# BreakoutBoard.net
KiCad netlist of a schematic drawn in EAGLE
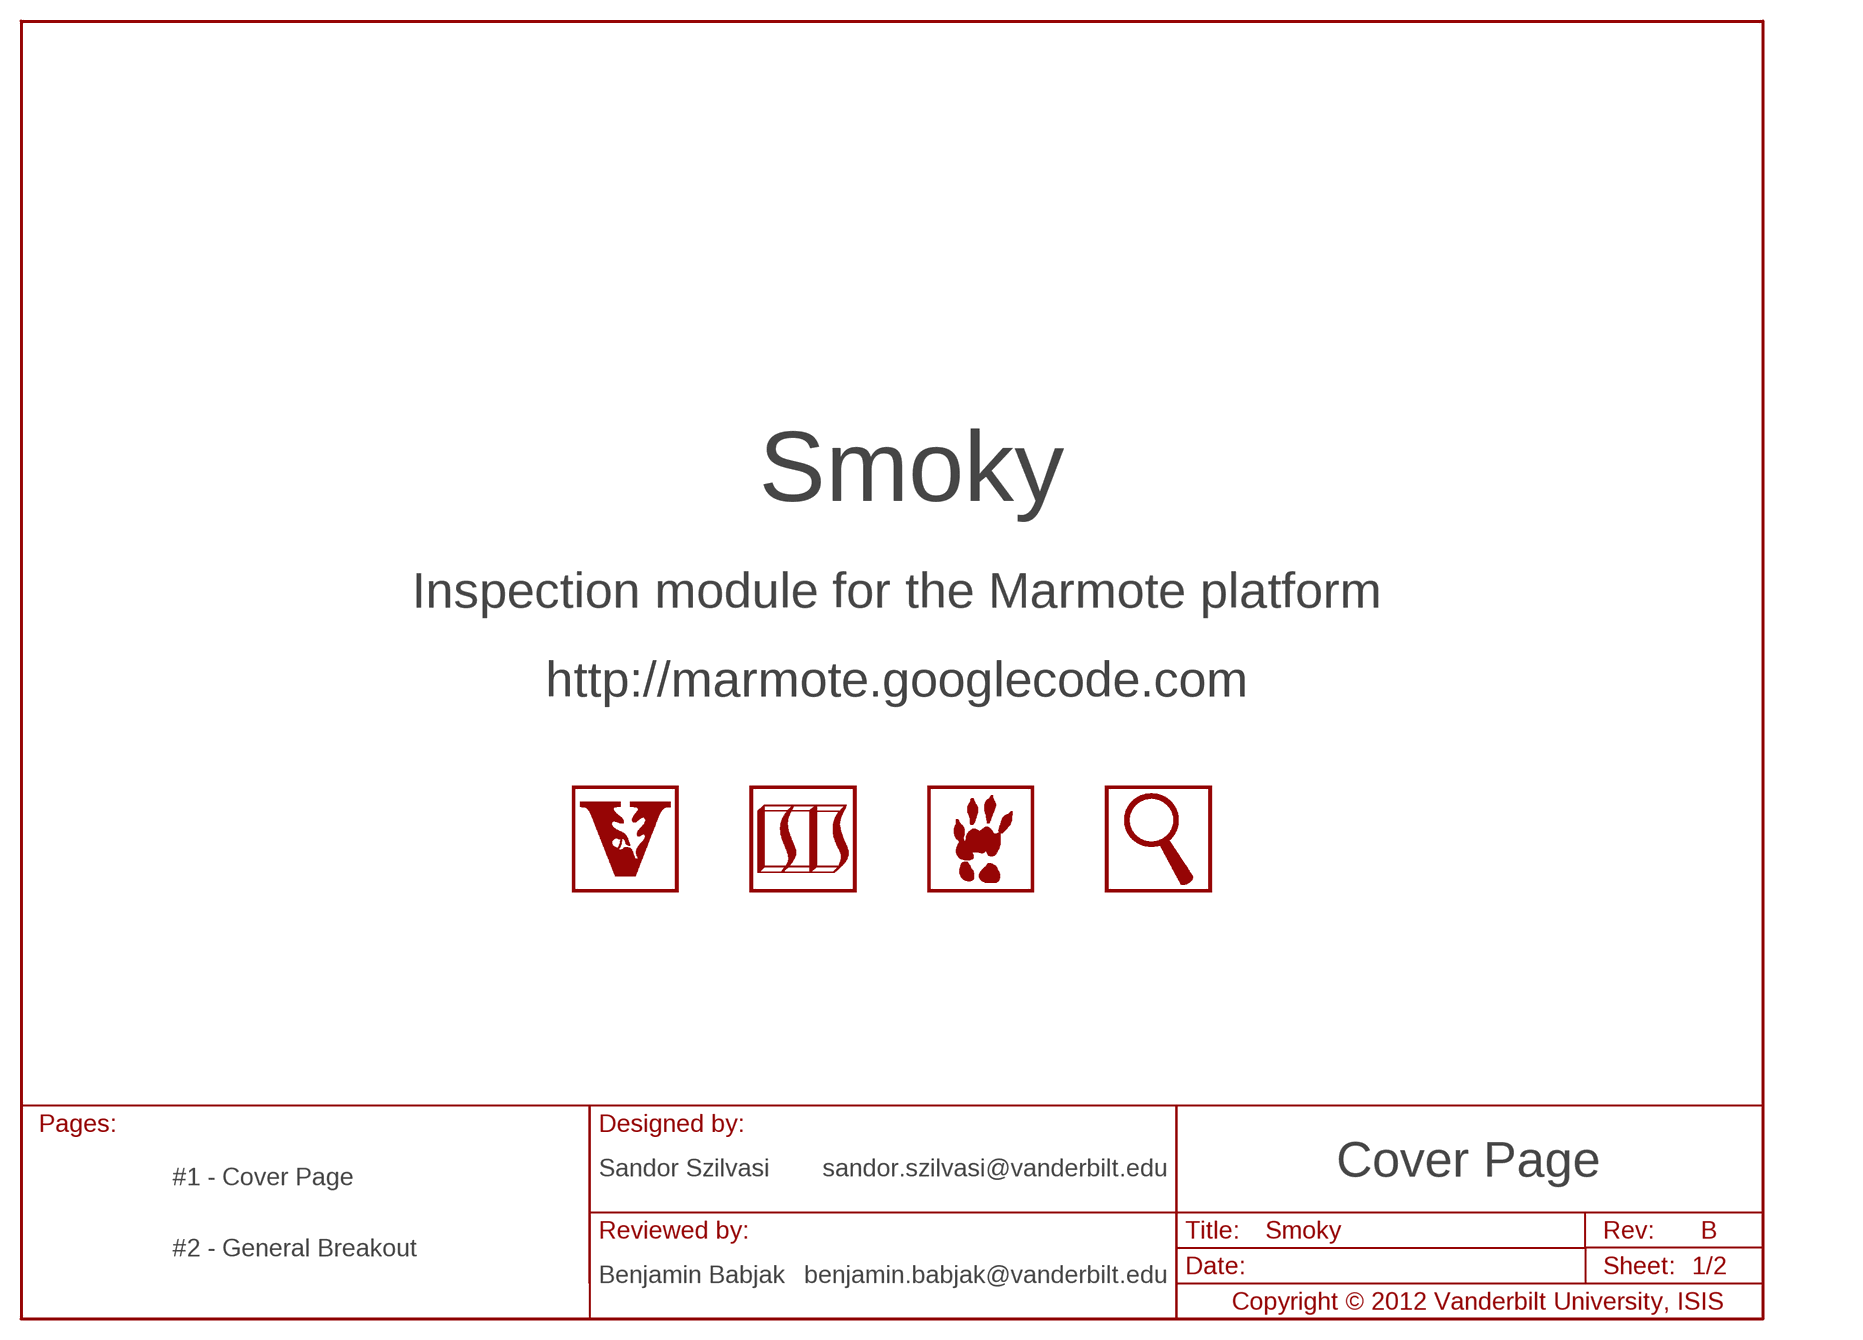
[diagram p0: schematic, sheet 1]
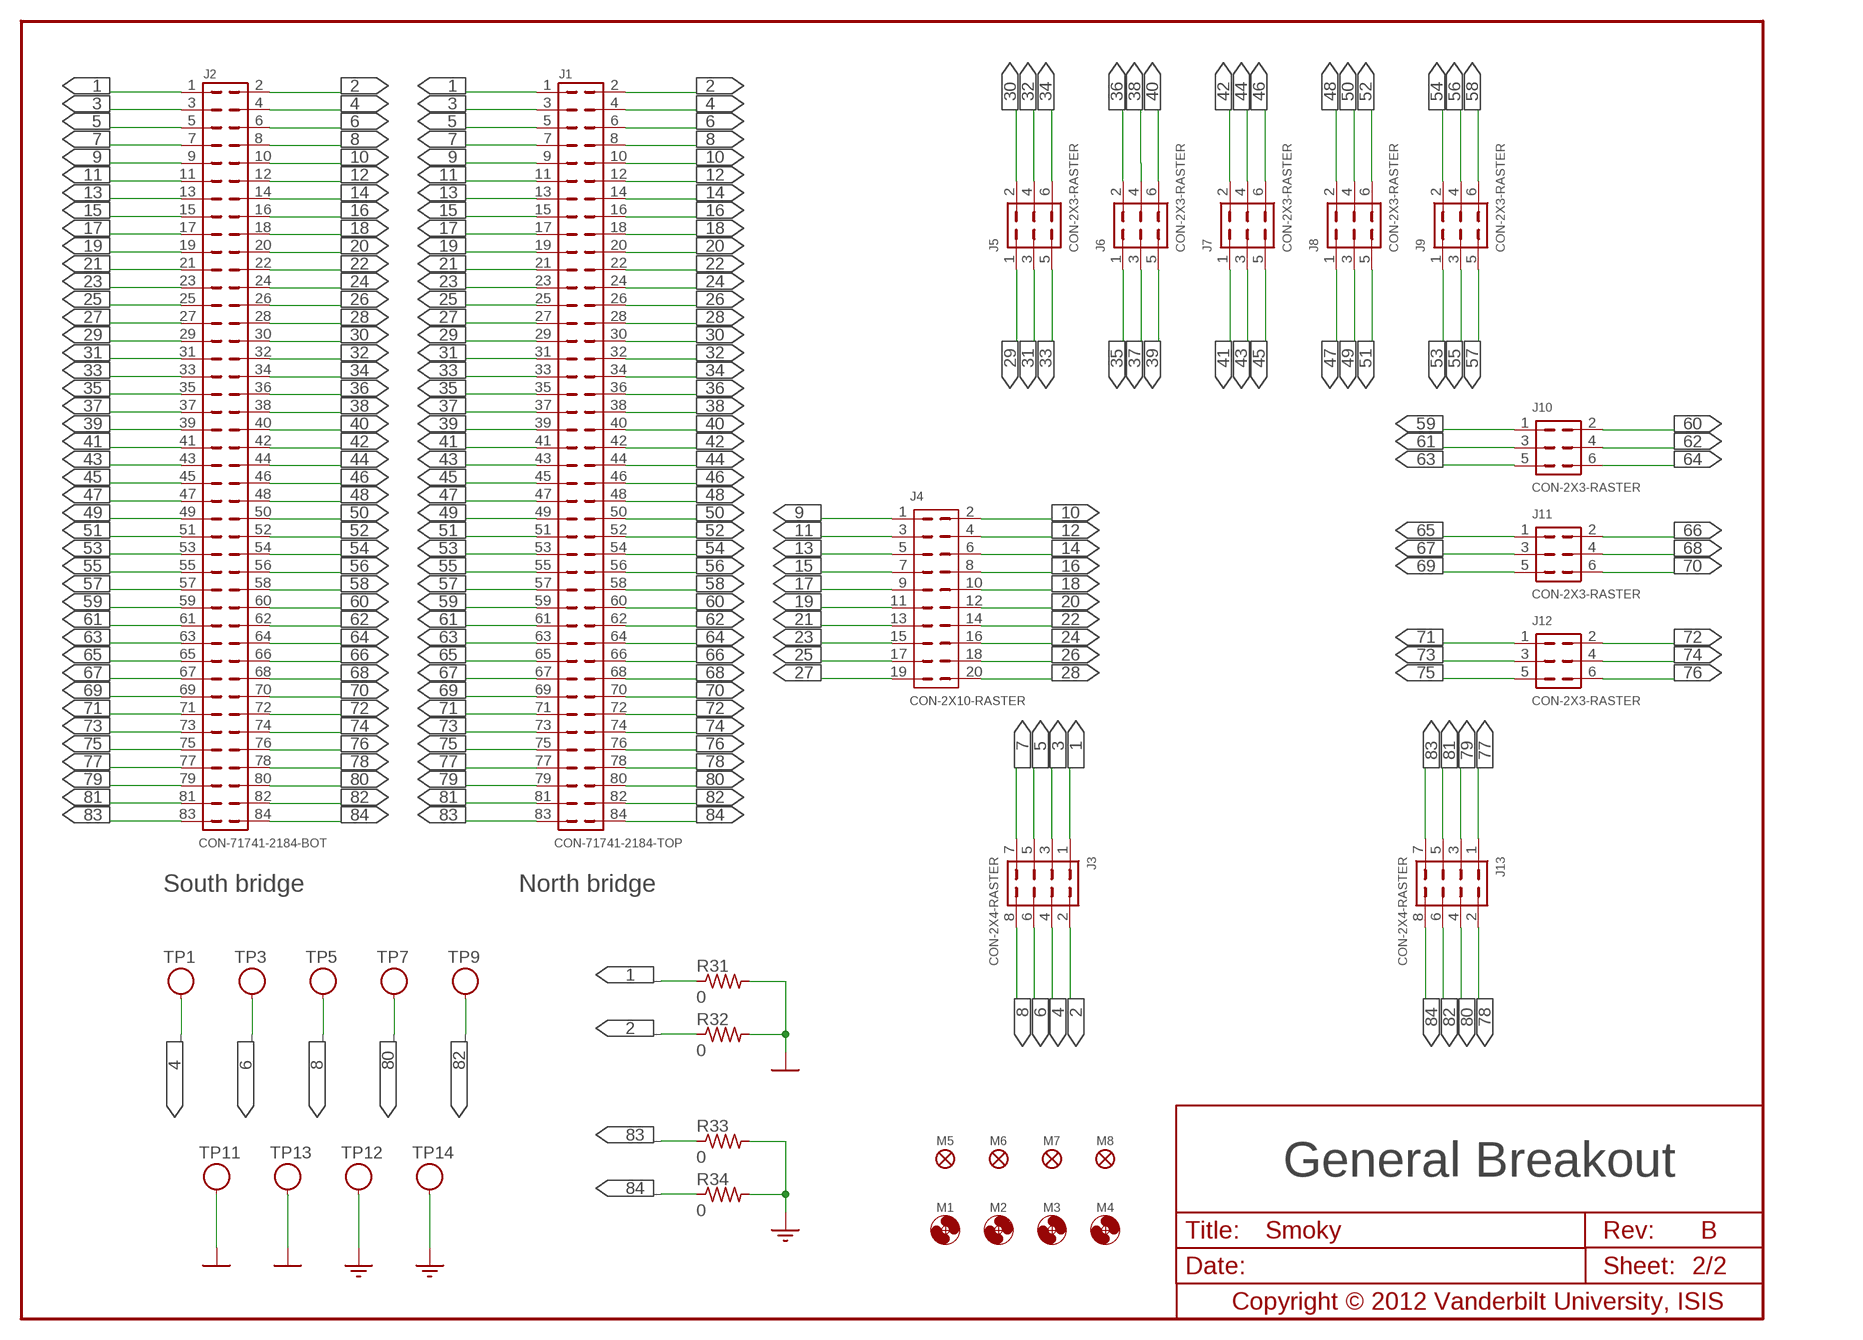
[diagram p1: schematic, sheet 2]

(export (version "E")
  (design (tool "Eeschema 10.0.6"))
  (components
    (comp (ref "LOGO1")
      (value "LOGO-MAGNIFYING-GLASS-600MIL-10MM-SS")
      (footprint "eagle-import:LOGO-MAGNIFYING-GLASS-10MM-SILKSCREEN")
      (libsource (lib "eagle-import") (part "LOGO-MAGNIFYING-GLASS-600MIL-10MM-SS"))
    )
    (comp (ref "LOGO5")
      (value "LOGO-VANDERBILT-600MIL-10MM-SS")
      (footprint "eagle-import:LOGO-VANDERBILT-10MM-SILKSCREEN")
      (libsource (lib "eagle-import") (part "LOGO-VANDERBILT-600MIL-10MM-SS"))
    )
    (comp (ref "LOGO6")
      (value "LOGO-ISIS-600MIL-10MM-SS")
      (footprint "eagle-import:LOGO-ISIS-10MM-SILKSCREEN")
      (libsource (lib "eagle-import") (part "LOGO-ISIS-600MIL-10MM-SS"))
    )
    (comp (ref "LOGO7")
      (value "LOGO-MARMOTE-600MIL-10MM-SS")
      (footprint "eagle-import:LOGO-MARMOTE-10MM-SILKSCREEN")
      (libsource (lib "eagle-import") (part "LOGO-MARMOTE-600MIL-10MM-SS"))
    )
    (comp (ref "J1")
      (value "CON-71741-2184-TOP")
      (footprint "eagle-import:71741-0002")
      (fields (field (name "MF") "Molex") (field (name "MPN") "71741-0002"))
      (libsource (lib "eagle-import") (part "CON-7174184-TOP-21"))
    )
    (comp (ref "J2")
      (value "CON-71741-2184-BOT")
      (footprint "eagle-import:71742-3003-BOT")
      (fields (field (name "MF") "Molex") (field (name "MPN") "71742-3003"))
      (libsource (lib "eagle-import") (part "CON-7174184-BOT-21"))
    )
    (comp (ref "J3")
      (value "CON-2X4-RASTER")
      (footprint "eagle-import:2X8")
      (libsource (lib "eagle-import") (part "CON-2X4-RASTER"))
    )
    (comp (ref "J4")
      (value "CON-2X10-RASTER")
      (footprint "eagle-import:2X20")
      (libsource (lib "eagle-import") (part "CON-2X10-RASTER"))
    )
    (comp (ref "J5")
      (value "CON-2X3-RASTER")
      (footprint "eagle-import:2X6")
      (libsource (lib "eagle-import") (part "CON-2X3-RASTER"))
    )
    (comp (ref "J6")
      (value "CON-2X3-RASTER")
      (footprint "eagle-import:2X6")
      (libsource (lib "eagle-import") (part "CON-2X3-RASTER"))
    )
    (comp (ref "J7")
      (value "CON-2X3-RASTER")
      (footprint "eagle-import:2X6")
      (libsource (lib "eagle-import") (part "CON-2X3-RASTER"))
    )
    (comp (ref "J8")
      (value "CON-2X3-RASTER")
      (footprint "eagle-import:2X6")
      (libsource (lib "eagle-import") (part "CON-2X3-RASTER"))
    )
    (comp (ref "J9")
      (value "CON-2X3-RASTER")
      (footprint "eagle-import:2X6")
      (libsource (lib "eagle-import") (part "CON-2X3-RASTER"))
    )
    (comp (ref "J10")
      (value "CON-2X3-RASTER")
      (footprint "eagle-import:2X6")
      (libsource (lib "eagle-import") (part "CON-2X3-RASTER"))
    )
    (comp (ref "J11")
      (value "CON-2X3-RASTER")
      (footprint "eagle-import:2X6")
      (libsource (lib "eagle-import") (part "CON-2X3-RASTER"))
    )
    (comp (ref "J12")
      (value "CON-2X3-RASTER")
      (footprint "eagle-import:2X6")
      (libsource (lib "eagle-import") (part "CON-2X3-RASTER"))
    )
    (comp (ref "J13")
      (value "CON-2X4-RASTER")
      (footprint "eagle-import:2X8")
      (libsource (lib "eagle-import") (part "CON-2X4-RASTER"))
    )
    (comp (ref "M1")
      (value "MOUNT-HOLE3.3")
      (footprint "eagle-import:3,3")
      (libsource (lib "eagle-import") (part "MOUNT-HOLE3.3"))
    )
    (comp (ref "M2")
      (value "MOUNT-HOLE3.3")
      (footprint "eagle-import:3,3")
      (libsource (lib "eagle-import") (part "MOUNT-HOLE3.3"))
    )
    (comp (ref "M3")
      (value "MOUNT-HOLE3.3")
      (footprint "eagle-import:3,3")
      (libsource (lib "eagle-import") (part "MOUNT-HOLE3.3"))
    )
    (comp (ref "M4")
      (value "MOUNT-HOLE3.3")
      (footprint "eagle-import:3,3")
      (libsource (lib "eagle-import") (part "MOUNT-HOLE3.3"))
    )
    (comp (ref "M5")
      (value "FIDUCIAL1X2")
      (footprint "eagle-import:FIDUCIAL-1X2")
      (libsource (lib "eagle-import") (part "FIDUCIAL1X2"))
    )
    (comp (ref "M6")
      (value "FIDUCIAL1X2")
      (footprint "eagle-import:FIDUCIAL-1X2")
      (libsource (lib "eagle-import") (part "FIDUCIAL1X2"))
    )
    (comp (ref "M7")
      (value "FIDUCIAL1X2")
      (footprint "eagle-import:FIDUCIAL-1X2")
      (libsource (lib "eagle-import") (part "FIDUCIAL1X2"))
    )
    (comp (ref "M8")
      (value "FIDUCIAL1X2")
      (footprint "eagle-import:FIDUCIAL-1X2")
      (libsource (lib "eagle-import") (part "FIDUCIAL1X2"))
    )
    (comp (ref "R31")
      (value "0")
      (footprint "eagle-import:R0805")
      (libsource (lib "eagle-import") (part "R0805"))
    )
    (comp (ref "R32")
      (value "0")
      (footprint "eagle-import:R0805")
      (libsource (lib "eagle-import") (part "R0805"))
    )
    (comp (ref "R33")
      (value "0")
      (footprint "eagle-import:R0805")
      (libsource (lib "eagle-import") (part "R0805"))
    )
    (comp (ref "R34")
      (value "0")
      (footprint "eagle-import:R0805")
      (libsource (lib "eagle-import") (part "R0805"))
    )
    (comp (ref "TP1")
      (value "TESTPOINT-BLUE")
      (footprint "eagle-import:TESTPOINT")
      (fields (field (name "MF") "Keystone") (field (name "MPN") "5122"))
      (libsource (lib "eagle-import") (part "TESTPOINT-BLUE"))
    )
    (comp (ref "TP3")
      (value "TESTPOINT-BLUE")
      (footprint "eagle-import:TESTPOINT")
      (fields (field (name "MF") "Keystone") (field (name "MPN") "5122"))
      (libsource (lib "eagle-import") (part "TESTPOINT-BLUE"))
    )
    (comp (ref "TP5")
      (value "TESTPOINT-BLUE")
      (footprint "eagle-import:TESTPOINT")
      (fields (field (name "MF") "Keystone") (field (name "MPN") "5122"))
      (libsource (lib "eagle-import") (part "TESTPOINT-BLUE"))
    )
    (comp (ref "TP7")
      (value "TESTPOINT-GREEN")
      (footprint "eagle-import:TESTPOINT")
      (fields (field (name "MF") "Keystone") (field (name "MPN") "5121"))
      (libsource (lib "eagle-import") (part "TESTPOINT-GREEN"))
    )
    (comp (ref "TP9")
      (value "TESTPOINT-GREEN")
      (footprint "eagle-import:TESTPOINT")
      (fields (field (name "MF") "Keystone") (field (name "MPN") "5121"))
      (libsource (lib "eagle-import") (part "TESTPOINT-GREEN"))
    )
    (comp (ref "TP11")
      (value "TESTPOINT-YELLOW")
      (footprint "eagle-import:TESTPOINT")
      (fields (field (name "MF") "Keystone") (field (name "MPN") "5009"))
      (libsource (lib "eagle-import") (part "TESTPOINT-YELLOW"))
    )
    (comp (ref "TP12")
      (value "TESTPOINT-YELLOW")
      (footprint "eagle-import:TESTPOINT")
      (fields (field (name "MF") "Keystone") (field (name "MPN") "5009"))
      (libsource (lib "eagle-import") (part "TESTPOINT-YELLOW"))
    )
    (comp (ref "TP13")
      (value "TESTPOINT-YELLOW")
      (footprint "eagle-import:TESTPOINT")
      (fields (field (name "MF") "Keystone") (field (name "MPN") "5009"))
      (libsource (lib "eagle-import") (part "TESTPOINT-YELLOW"))
    )
    (comp (ref "TP14")
      (value "TESTPOINT-YELLOW")
      (footprint "eagle-import:TESTPOINT")
      (fields (field (name "MF") "Keystone") (field (name "MPN") "5009"))
      (libsource (lib "eagle-import") (part "TESTPOINT-YELLOW"))
    )
  )
  (nets
    (net (code "1") (name "1") (class "Default")
      (node (ref "J1") (pin "1") (pinfunction "1_1") (pintype "passive"))
      (node (ref "J2") (pin "1") (pinfunction "1_1") (pintype "passive"))
      (node (ref "J3") (pin "1") (pinfunction "1_1") (pintype "passive"))
      (node (ref "R31") (pin "1") (pinfunction "1_1") (pintype "passive"))
    )
    (net (code "2") (name "2") (class "Default")
      (node (ref "J1") (pin "2") (pinfunction "2_2") (pintype "passive"))
      (node (ref "J2") (pin "2") (pinfunction "2_2") (pintype "passive"))
      (node (ref "J3") (pin "2") (pinfunction "2_2") (pintype "passive"))
      (node (ref "R32") (pin "1") (pinfunction "1_1") (pintype "passive"))
    )
    (net (code "3") (name "3") (class "Default")
      (node (ref "J1") (pin "3") (pinfunction "3_3") (pintype "passive"))
      (node (ref "J2") (pin "3") (pinfunction "3_3") (pintype "passive"))
      (node (ref "J3") (pin "3") (pinfunction "3_3") (pintype "passive"))
    )
    (net (code "4") (name "4") (class "Default")
      (node (ref "J1") (pin "4") (pinfunction "4_4") (pintype "passive"))
      (node (ref "J2") (pin "4") (pinfunction "4_4") (pintype "passive"))
      (node (ref "J3") (pin "4") (pinfunction "4_4") (pintype "passive"))
      (node (ref "TP1") (pin "1") (pinfunction "1_1") (pintype "power_in"))
    )
    (net (code "5") (name "5") (class "Default")
      (node (ref "J1") (pin "5") (pinfunction "5_5") (pintype "passive"))
      (node (ref "J2") (pin "5") (pinfunction "5_5") (pintype "passive"))
      (node (ref "J3") (pin "5") (pinfunction "5_5") (pintype "passive"))
    )
    (net (code "6") (name "6") (class "Default")
      (node (ref "J1") (pin "6") (pinfunction "6_6") (pintype "passive"))
      (node (ref "J2") (pin "6") (pinfunction "6_6") (pintype "passive"))
      (node (ref "J3") (pin "6") (pinfunction "6_6") (pintype "passive"))
      (node (ref "TP3") (pin "1") (pinfunction "1_1") (pintype "power_in"))
    )
    (net (code "7") (name "7") (class "Default")
      (node (ref "J1") (pin "7") (pinfunction "7_7") (pintype "passive"))
      (node (ref "J2") (pin "7") (pinfunction "7_7") (pintype "passive"))
      (node (ref "J3") (pin "7") (pinfunction "7_7") (pintype "passive"))
    )
    (net (code "8") (name "8") (class "Default")
      (node (ref "J1") (pin "8") (pinfunction "8_8") (pintype "passive"))
      (node (ref "J2") (pin "8") (pinfunction "8_8") (pintype "passive"))
      (node (ref "J3") (pin "8") (pinfunction "8_8") (pintype "passive"))
      (node (ref "TP5") (pin "1") (pinfunction "1_1") (pintype "power_in"))
    )
    (net (code "9") (name "9") (class "Default")
      (node (ref "J1") (pin "9") (pinfunction "9_9") (pintype "passive"))
      (node (ref "J2") (pin "9") (pinfunction "9_9") (pintype "passive"))
      (node (ref "J4") (pin "1") (pinfunction "1_1") (pintype "passive"))
    )
    (net (code "10") (name "10") (class "Default")
      (node (ref "J1") (pin "10") (pinfunction "10_10") (pintype "passive"))
      (node (ref "J2") (pin "10") (pinfunction "10_10") (pintype "passive"))
      (node (ref "J4") (pin "2") (pinfunction "2_2") (pintype "passive"))
    )
    (net (code "11") (name "11") (class "Default")
      (node (ref "J1") (pin "11") (pinfunction "11_11") (pintype "passive"))
      (node (ref "J2") (pin "11") (pinfunction "11_11") (pintype "passive"))
      (node (ref "J4") (pin "3") (pinfunction "3_3") (pintype "passive"))
    )
    (net (code "12") (name "12") (class "Default")
      (node (ref "J1") (pin "12") (pinfunction "12_12") (pintype "passive"))
      (node (ref "J2") (pin "12") (pinfunction "12_12") (pintype "passive"))
      (node (ref "J4") (pin "4") (pinfunction "4_4") (pintype "passive"))
    )
    (net (code "13") (name "13") (class "Default")
      (node (ref "J1") (pin "13") (pinfunction "13_13") (pintype "passive"))
      (node (ref "J2") (pin "13") (pinfunction "13_13") (pintype "passive"))
      (node (ref "J4") (pin "5") (pinfunction "5_5") (pintype "passive"))
    )
    (net (code "14") (name "14") (class "Default")
      (node (ref "J1") (pin "14") (pinfunction "14_14") (pintype "passive"))
      (node (ref "J2") (pin "14") (pinfunction "14_14") (pintype "passive"))
      (node (ref "J4") (pin "6") (pinfunction "6_6") (pintype "passive"))
    )
    (net (code "15") (name "15") (class "Default")
      (node (ref "J1") (pin "15") (pinfunction "15_15") (pintype "passive"))
      (node (ref "J2") (pin "15") (pinfunction "15_15") (pintype "passive"))
      (node (ref "J4") (pin "7") (pinfunction "7_7") (pintype "passive"))
    )
    (net (code "16") (name "16") (class "Default")
      (node (ref "J1") (pin "16") (pinfunction "16_16") (pintype "passive"))
      (node (ref "J2") (pin "16") (pinfunction "16_16") (pintype "passive"))
      (node (ref "J4") (pin "8") (pinfunction "8_8") (pintype "passive"))
    )
    (net (code "17") (name "17") (class "Default")
      (node (ref "J1") (pin "17") (pinfunction "17_17") (pintype "passive"))
      (node (ref "J2") (pin "17") (pinfunction "17_17") (pintype "passive"))
      (node (ref "J4") (pin "9") (pinfunction "9_9") (pintype "passive"))
    )
    (net (code "18") (name "18") (class "Default")
      (node (ref "J1") (pin "18") (pinfunction "18_18") (pintype "passive"))
      (node (ref "J2") (pin "18") (pinfunction "18_18") (pintype "passive"))
      (node (ref "J4") (pin "10") (pinfunction "10_10") (pintype "passive"))
    )
    (net (code "19") (name "19") (class "Default")
      (node (ref "J1") (pin "19") (pinfunction "19_19") (pintype "passive"))
      (node (ref "J2") (pin "19") (pinfunction "19_19") (pintype "passive"))
      (node (ref "J4") (pin "11") (pinfunction "11_11") (pintype "passive"))
    )
    (net (code "20") (name "20") (class "Default")
      (node (ref "J1") (pin "20") (pinfunction "20_20") (pintype "passive"))
      (node (ref "J2") (pin "20") (pinfunction "20_20") (pintype "passive"))
      (node (ref "J4") (pin "12") (pinfunction "12_12") (pintype "passive"))
    )
    (net (code "21") (name "21") (class "Default")
      (node (ref "J1") (pin "21") (pinfunction "21_21") (pintype "passive"))
      (node (ref "J2") (pin "21") (pinfunction "21_21") (pintype "passive"))
      (node (ref "J4") (pin "13") (pinfunction "13_13") (pintype "passive"))
    )
    (net (code "22") (name "22") (class "Default")
      (node (ref "J1") (pin "22") (pinfunction "22_22") (pintype "passive"))
      (node (ref "J2") (pin "22") (pinfunction "22_22") (pintype "passive"))
      (node (ref "J4") (pin "14") (pinfunction "14_14") (pintype "passive"))
    )
    (net (code "23") (name "23") (class "Default")
      (node (ref "J1") (pin "23") (pinfunction "23_23") (pintype "passive"))
      (node (ref "J2") (pin "23") (pinfunction "23_23") (pintype "passive"))
      (node (ref "J4") (pin "15") (pinfunction "15_15") (pintype "passive"))
    )
    (net (code "24") (name "24") (class "Default")
      (node (ref "J1") (pin "24") (pinfunction "24_24") (pintype "passive"))
      (node (ref "J2") (pin "24") (pinfunction "24_24") (pintype "passive"))
      (node (ref "J4") (pin "16") (pinfunction "16_16") (pintype "passive"))
    )
    (net (code "25") (name "25") (class "Default")
      (node (ref "J1") (pin "25") (pinfunction "25_25") (pintype "passive"))
      (node (ref "J2") (pin "25") (pinfunction "25_25") (pintype "passive"))
      (node (ref "J4") (pin "17") (pinfunction "17_17") (pintype "passive"))
    )
    (net (code "26") (name "26") (class "Default")
      (node (ref "J1") (pin "26") (pinfunction "26_26") (pintype "passive"))
      (node (ref "J2") (pin "26") (pinfunction "26_26") (pintype "passive"))
      (node (ref "J4") (pin "18") (pinfunction "18_18") (pintype "passive"))
    )
    (net (code "27") (name "27") (class "Default")
      (node (ref "J1") (pin "27") (pinfunction "27_27") (pintype "passive"))
      (node (ref "J2") (pin "27") (pinfunction "27_27") (pintype "passive"))
      (node (ref "J4") (pin "19") (pinfunction "19_19") (pintype "passive"))
    )
    (net (code "28") (name "28") (class "Default")
      (node (ref "J1") (pin "28") (pinfunction "28_28") (pintype "passive"))
      (node (ref "J2") (pin "28") (pinfunction "28_28") (pintype "passive"))
      (node (ref "J4") (pin "20") (pinfunction "20_20") (pintype "passive"))
    )
    (net (code "29") (name "29") (class "Default")
      (node (ref "J1") (pin "29") (pinfunction "29_29") (pintype "passive"))
      (node (ref "J2") (pin "29") (pinfunction "29_29") (pintype "passive"))
      (node (ref "J5") (pin "1") (pinfunction "1_1") (pintype "passive"))
    )
    (net (code "30") (name "30") (class "Default")
      (node (ref "J1") (pin "30") (pinfunction "30_30") (pintype "passive"))
      (node (ref "J2") (pin "30") (pinfunction "30_30") (pintype "passive"))
      (node (ref "J5") (pin "2") (pinfunction "2_2") (pintype "passive"))
    )
    (net (code "31") (name "31") (class "Default")
      (node (ref "J1") (pin "31") (pinfunction "31_31") (pintype "passive"))
      (node (ref "J2") (pin "31") (pinfunction "31_31") (pintype "passive"))
      (node (ref "J5") (pin "3") (pinfunction "3_3") (pintype "passive"))
    )
    (net (code "32") (name "32") (class "Default")
      (node (ref "J1") (pin "32") (pinfunction "32_32") (pintype "passive"))
      (node (ref "J2") (pin "32") (pinfunction "32_32") (pintype "passive"))
      (node (ref "J5") (pin "4") (pinfunction "4_4") (pintype "passive"))
    )
    (net (code "33") (name "33") (class "Default")
      (node (ref "J1") (pin "33") (pinfunction "33_33") (pintype "passive"))
      (node (ref "J2") (pin "33") (pinfunction "33_33") (pintype "passive"))
      (node (ref "J5") (pin "5") (pinfunction "5_5") (pintype "passive"))
    )
    (net (code "34") (name "34") (class "Default")
      (node (ref "J1") (pin "34") (pinfunction "34_34") (pintype "passive"))
      (node (ref "J2") (pin "34") (pinfunction "34_34") (pintype "passive"))
      (node (ref "J5") (pin "6") (pinfunction "6_6") (pintype "passive"))
    )
    (net (code "35") (name "35") (class "Default")
      (node (ref "J1") (pin "35") (pinfunction "35_35") (pintype "passive"))
      (node (ref "J2") (pin "35") (pinfunction "35_35") (pintype "passive"))
      (node (ref "J6") (pin "1") (pinfunction "1_1") (pintype "passive"))
    )
    (net (code "36") (name "36") (class "Default")
      (node (ref "J1") (pin "36") (pinfunction "36_36") (pintype "passive"))
      (node (ref "J2") (pin "36") (pinfunction "36_36") (pintype "passive"))
      (node (ref "J6") (pin "2") (pinfunction "2_2") (pintype "passive"))
    )
    (net (code "37") (name "37") (class "Default")
      (node (ref "J1") (pin "37") (pinfunction "37_37") (pintype "passive"))
      (node (ref "J2") (pin "37") (pinfunction "37_37") (pintype "passive"))
      (node (ref "J6") (pin "3") (pinfunction "3_3") (pintype "passive"))
    )
    (net (code "38") (name "38") (class "Default")
      (node (ref "J1") (pin "38") (pinfunction "38_38") (pintype "passive"))
      (node (ref "J2") (pin "38") (pinfunction "38_38") (pintype "passive"))
      (node (ref "J6") (pin "4") (pinfunction "4_4") (pintype "passive"))
    )
    (net (code "39") (name "39") (class "Default")
      (node (ref "J1") (pin "39") (pinfunction "39_39") (pintype "passive"))
      (node (ref "J2") (pin "39") (pinfunction "39_39") (pintype "passive"))
      (node (ref "J6") (pin "5") (pinfunction "5_5") (pintype "passive"))
    )
    (net (code "40") (name "40") (class "Default")
      (node (ref "J1") (pin "40") (pinfunction "40_40") (pintype "passive"))
      (node (ref "J2") (pin "40") (pinfunction "40_40") (pintype "passive"))
      (node (ref "J6") (pin "6") (pinfunction "6_6") (pintype "passive"))
    )
    (net (code "41") (name "41") (class "Default")
      (node (ref "J1") (pin "41") (pinfunction "41_41") (pintype "passive"))
      (node (ref "J2") (pin "41") (pinfunction "41_41") (pintype "passive"))
      (node (ref "J7") (pin "1") (pinfunction "1_1") (pintype "passive"))
    )
    (net (code "42") (name "42") (class "Default")
      (node (ref "J1") (pin "42") (pinfunction "42_42") (pintype "passive"))
      (node (ref "J2") (pin "42") (pinfunction "42_42") (pintype "passive"))
      (node (ref "J7") (pin "2") (pinfunction "2_2") (pintype "passive"))
    )
    (net (code "43") (name "43") (class "Default")
      (node (ref "J1") (pin "43") (pinfunction "43_43") (pintype "passive"))
      (node (ref "J2") (pin "43") (pinfunction "43_43") (pintype "passive"))
      (node (ref "J7") (pin "3") (pinfunction "3_3") (pintype "passive"))
    )
    (net (code "44") (name "44") (class "Default")
      (node (ref "J1") (pin "44") (pinfunction "44_44") (pintype "passive"))
      (node (ref "J2") (pin "44") (pinfunction "44_44") (pintype "passive"))
      (node (ref "J7") (pin "4") (pinfunction "4_4") (pintype "passive"))
    )
    (net (code "45") (name "45") (class "Default")
      (node (ref "J1") (pin "45") (pinfunction "45_45") (pintype "passive"))
      (node (ref "J2") (pin "45") (pinfunction "45_45") (pintype "passive"))
      (node (ref "J7") (pin "5") (pinfunction "5_5") (pintype "passive"))
    )
    (net (code "46") (name "46") (class "Default")
      (node (ref "J1") (pin "46") (pinfunction "46_46") (pintype "passive"))
      (node (ref "J2") (pin "46") (pinfunction "46_46") (pintype "passive"))
      (node (ref "J7") (pin "6") (pinfunction "6_6") (pintype "passive"))
    )
    (net (code "47") (name "47") (class "Default")
      (node (ref "J1") (pin "47") (pinfunction "47_47") (pintype "passive"))
      (node (ref "J2") (pin "47") (pinfunction "47_47") (pintype "passive"))
      (node (ref "J8") (pin "1") (pinfunction "1_1") (pintype "passive"))
    )
    (net (code "48") (name "48") (class "Default")
      (node (ref "J1") (pin "48") (pinfunction "48_48") (pintype "passive"))
      (node (ref "J2") (pin "48") (pinfunction "48_48") (pintype "passive"))
      (node (ref "J8") (pin "2") (pinfunction "2_2") (pintype "passive"))
    )
    (net (code "49") (name "49") (class "Default")
      (node (ref "J1") (pin "49") (pinfunction "49_49") (pintype "passive"))
      (node (ref "J2") (pin "49") (pinfunction "49_49") (pintype "passive"))
      (node (ref "J8") (pin "3") (pinfunction "3_3") (pintype "passive"))
    )
    (net (code "50") (name "50") (class "Default")
      (node (ref "J1") (pin "50") (pinfunction "50_50") (pintype "passive"))
      (node (ref "J2") (pin "50") (pinfunction "50_50") (pintype "passive"))
      (node (ref "J8") (pin "4") (pinfunction "4_4") (pintype "passive"))
    )
    (net (code "51") (name "51") (class "Default")
      (node (ref "J1") (pin "51") (pinfunction "51_51") (pintype "passive"))
      (node (ref "J2") (pin "51") (pinfunction "51_51") (pintype "passive"))
      (node (ref "J8") (pin "5") (pinfunction "5_5") (pintype "passive"))
    )
    (net (code "52") (name "52") (class "Default")
      (node (ref "J1") (pin "52") (pinfunction "52_52") (pintype "passive"))
      (node (ref "J2") (pin "52") (pinfunction "52_52") (pintype "passive"))
      (node (ref "J8") (pin "6") (pinfunction "6_6") (pintype "passive"))
    )
    (net (code "53") (name "53") (class "Default")
      (node (ref "J1") (pin "53") (pinfunction "53_53") (pintype "passive"))
      (node (ref "J2") (pin "53") (pinfunction "53_53") (pintype "passive"))
      (node (ref "J9") (pin "1") (pinfunction "1_1") (pintype "passive"))
    )
    (net (code "54") (name "54") (class "Default")
      (node (ref "J1") (pin "54") (pinfunction "54_54") (pintype "passive"))
      (node (ref "J2") (pin "54") (pinfunction "54_54") (pintype "passive"))
      (node (ref "J9") (pin "2") (pinfunction "2_2") (pintype "passive"))
    )
    (net (code "55") (name "55") (class "Default")
      (node (ref "J1") (pin "55") (pinfunction "55_55") (pintype "passive"))
      (node (ref "J2") (pin "55") (pinfunction "55_55") (pintype "passive"))
      (node (ref "J9") (pin "3") (pinfunction "3_3") (pintype "passive"))
    )
    (net (code "56") (name "56") (class "Default")
      (node (ref "J1") (pin "56") (pinfunction "56_56") (pintype "passive"))
      (node (ref "J2") (pin "56") (pinfunction "56_56") (pintype "passive"))
      (node (ref "J9") (pin "4") (pinfunction "4_4") (pintype "passive"))
    )
    (net (code "57") (name "57") (class "Default")
      (node (ref "J1") (pin "57") (pinfunction "57_57") (pintype "passive"))
      (node (ref "J2") (pin "57") (pinfunction "57_57") (pintype "passive"))
      (node (ref "J9") (pin "5") (pinfunction "5_5") (pintype "passive"))
    )
    (net (code "58") (name "58") (class "Default")
      (node (ref "J1") (pin "58") (pinfunction "58_58") (pintype "passive"))
      (node (ref "J2") (pin "58") (pinfunction "58_58") (pintype "passive"))
      (node (ref "J9") (pin "6") (pinfunction "6_6") (pintype "passive"))
    )
    (net (code "59") (name "59") (class "Default")
      (node (ref "J1") (pin "59") (pinfunction "59_59") (pintype "passive"))
      (node (ref "J10") (pin "1") (pinfunction "1_1") (pintype "passive"))
      (node (ref "J2") (pin "59") (pinfunction "59_59") (pintype "passive"))
    )
    (net (code "60") (name "60") (class "Default")
      (node (ref "J1") (pin "60") (pinfunction "60_60") (pintype "passive"))
      (node (ref "J10") (pin "2") (pinfunction "2_2") (pintype "passive"))
      (node (ref "J2") (pin "60") (pinfunction "60_60") (pintype "passive"))
    )
    (net (code "61") (name "61") (class "Default")
      (node (ref "J1") (pin "61") (pinfunction "61_61") (pintype "passive"))
      (node (ref "J10") (pin "3") (pinfunction "3_3") (pintype "passive"))
      (node (ref "J2") (pin "61") (pinfunction "61_61") (pintype "passive"))
    )
    (net (code "62") (name "62") (class "Default")
      (node (ref "J1") (pin "62") (pinfunction "62_62") (pintype "passive"))
      (node (ref "J10") (pin "4") (pinfunction "4_4") (pintype "passive"))
      (node (ref "J2") (pin "62") (pinfunction "62_62") (pintype "passive"))
    )
    (net (code "63") (name "63") (class "Default")
      (node (ref "J1") (pin "63") (pinfunction "63_63") (pintype "passive"))
      (node (ref "J10") (pin "5") (pinfunction "5_5") (pintype "passive"))
      (node (ref "J2") (pin "63") (pinfunction "63_63") (pintype "passive"))
    )
    (net (code "64") (name "64") (class "Default")
      (node (ref "J1") (pin "64") (pinfunction "64_64") (pintype "passive"))
      (node (ref "J10") (pin "6") (pinfunction "6_6") (pintype "passive"))
      (node (ref "J2") (pin "64") (pinfunction "64_64") (pintype "passive"))
    )
    (net (code "65") (name "65") (class "Default")
      (node (ref "J1") (pin "65") (pinfunction "65_65") (pintype "passive"))
      (node (ref "J11") (pin "1") (pinfunction "1_1") (pintype "passive"))
      (node (ref "J2") (pin "65") (pinfunction "65_65") (pintype "passive"))
    )
    (net (code "66") (name "66") (class "Default")
      (node (ref "J1") (pin "66") (pinfunction "66_66") (pintype "passive"))
      (node (ref "J11") (pin "2") (pinfunction "2_2") (pintype "passive"))
      (node (ref "J2") (pin "66") (pinfunction "66_66") (pintype "passive"))
    )
    (net (code "67") (name "67") (class "Default")
      (node (ref "J1") (pin "67") (pinfunction "67_67") (pintype "passive"))
      (node (ref "J11") (pin "3") (pinfunction "3_3") (pintype "passive"))
      (node (ref "J2") (pin "67") (pinfunction "67_67") (pintype "passive"))
    )
    (net (code "68") (name "68") (class "Default")
      (node (ref "J1") (pin "68") (pinfunction "68_68") (pintype "passive"))
      (node (ref "J11") (pin "4") (pinfunction "4_4") (pintype "passive"))
      (node (ref "J2") (pin "68") (pinfunction "68_68") (pintype "passive"))
    )
    (net (code "69") (name "69") (class "Default")
      (node (ref "J1") (pin "69") (pinfunction "69_69") (pintype "passive"))
      (node (ref "J11") (pin "5") (pinfunction "5_5") (pintype "passive"))
      (node (ref "J2") (pin "69") (pinfunction "69_69") (pintype "passive"))
    )
    (net (code "70") (name "70") (class "Default")
      (node (ref "J1") (pin "70") (pinfunction "70_70") (pintype "passive"))
      (node (ref "J11") (pin "6") (pinfunction "6_6") (pintype "passive"))
      (node (ref "J2") (pin "70") (pinfunction "70_70") (pintype "passive"))
    )
    (net (code "71") (name "71") (class "Default")
      (node (ref "J1") (pin "71") (pinfunction "71_71") (pintype "passive"))
      (node (ref "J12") (pin "1") (pinfunction "1_1") (pintype "passive"))
      (node (ref "J2") (pin "71") (pinfunction "71_71") (pintype "passive"))
    )
    (net (code "72") (name "72") (class "Default")
      (node (ref "J1") (pin "72") (pinfunction "72_72") (pintype "passive"))
      (node (ref "J12") (pin "2") (pinfunction "2_2") (pintype "passive"))
      (node (ref "J2") (pin "72") (pinfunction "72_72") (pintype "passive"))
    )
    (net (code "73") (name "73") (class "Default")
      (node (ref "J1") (pin "73") (pinfunction "73_73") (pintype "passive"))
      (node (ref "J12") (pin "3") (pinfunction "3_3") (pintype "passive"))
      (node (ref "J2") (pin "73") (pinfunction "73_73") (pintype "passive"))
    )
    (net (code "74") (name "74") (class "Default")
      (node (ref "J1") (pin "74") (pinfunction "74_74") (pintype "passive"))
      (node (ref "J12") (pin "4") (pinfunction "4_4") (pintype "passive"))
      (node (ref "J2") (pin "74") (pinfunction "74_74") (pintype "passive"))
    )
    (net (code "75") (name "75") (class "Default")
      (node (ref "J1") (pin "75") (pinfunction "75_75") (pintype "passive"))
      (node (ref "J12") (pin "5") (pinfunction "5_5") (pintype "passive"))
      (node (ref "J2") (pin "75") (pinfunction "75_75") (pintype "passive"))
    )
    (net (code "76") (name "76") (class "Default")
      (node (ref "J1") (pin "76") (pinfunction "76_76") (pintype "passive"))
      (node (ref "J12") (pin "6") (pinfunction "6_6") (pintype "passive"))
      (node (ref "J2") (pin "76") (pinfunction "76_76") (pintype "passive"))
    )
    (net (code "77") (name "77") (class "Default")
      (node (ref "J1") (pin "77") (pinfunction "77_77") (pintype "passive"))
      (node (ref "J13") (pin "1") (pinfunction "1_1") (pintype "passive"))
      (node (ref "J2") (pin "77") (pinfunction "77_77") (pintype "passive"))
    )
    (net (code "78") (name "78") (class "Default")
      (node (ref "J1") (pin "78") (pinfunction "78_78") (pintype "passive"))
      (node (ref "J13") (pin "2") (pinfunction "2_2") (pintype "passive"))
      (node (ref "J2") (pin "78") (pinfunction "78_78") (pintype "passive"))
    )
    (net (code "79") (name "79") (class "Default")
      (node (ref "J1") (pin "79") (pinfunction "79_79") (pintype "passive"))
      (node (ref "J13") (pin "3") (pinfunction "3_3") (pintype "passive"))
      (node (ref "J2") (pin "79") (pinfunction "79_79") (pintype "passive"))
    )
    (net (code "80") (name "80") (class "Default")
      (node (ref "J1") (pin "80") (pinfunction "80_80") (pintype "passive"))
      (node (ref "J13") (pin "4") (pinfunction "4_4") (pintype "passive"))
      (node (ref "J2") (pin "80") (pinfunction "80_80") (pintype "passive"))
      (node (ref "TP7") (pin "1") (pinfunction "1_1") (pintype "power_in"))
    )
    (net (code "81") (name "81") (class "Default")
      (node (ref "J1") (pin "81") (pinfunction "81_81") (pintype "passive"))
      (node (ref "J13") (pin "5") (pinfunction "5_5") (pintype "passive"))
      (node (ref "J2") (pin "81") (pinfunction "81_81") (pintype "passive"))
    )
    (net (code "82") (name "82") (class "Default")
      (node (ref "J1") (pin "82") (pinfunction "82_82") (pintype "passive"))
      (node (ref "J13") (pin "6") (pinfunction "6_6") (pintype "passive"))
      (node (ref "J2") (pin "82") (pinfunction "82_82") (pintype "passive"))
      (node (ref "TP9") (pin "1") (pinfunction "1_1") (pintype "power_in"))
    )
    (net (code "83") (name "83") (class "Default")
      (node (ref "J1") (pin "83") (pinfunction "83_83") (pintype "passive"))
      (node (ref "J13") (pin "7") (pinfunction "7_7") (pintype "passive"))
      (node (ref "J2") (pin "83") (pinfunction "83_83") (pintype "passive"))
      (node (ref "R33") (pin "1") (pinfunction "1_1") (pintype "passive"))
    )
    (net (code "84") (name "84") (class "Default")
      (node (ref "J1") (pin "84") (pinfunction "84_84") (pintype "passive"))
      (node (ref "J13") (pin "8") (pinfunction "8_8") (pintype "passive"))
      (node (ref "J2") (pin "84") (pinfunction "84_84") (pintype "passive"))
      (node (ref "R34") (pin "1") (pinfunction "1_1") (pintype "passive"))
    )
    (net (code "85") (name "AGND") (class "Default")
      (node (ref "R33") (pin "2") (pinfunction "2_2") (pintype "passive"))
      (node (ref "R34") (pin "2") (pinfunction "2_2") (pintype "passive"))
      (node (ref "TP12") (pin "1") (pinfunction "1_1") (pintype "power_in"))
      (node (ref "TP14") (pin "1") (pinfunction "1_1") (pintype "power_in"))
    )
    (net (code "86") (name "DGND") (class "Default")
      (node (ref "R31") (pin "2") (pinfunction "2_2") (pintype "passive"))
      (node (ref "R32") (pin "2") (pinfunction "2_2") (pintype "passive"))
      (node (ref "TP11") (pin "1") (pinfunction "1_1") (pintype "power_in"))
      (node (ref "TP13") (pin "1") (pinfunction "1_1") (pintype "power_in"))
    )
  )
)
